# USB.net
KiCad netlist of a schematic drawn in Altium Designer
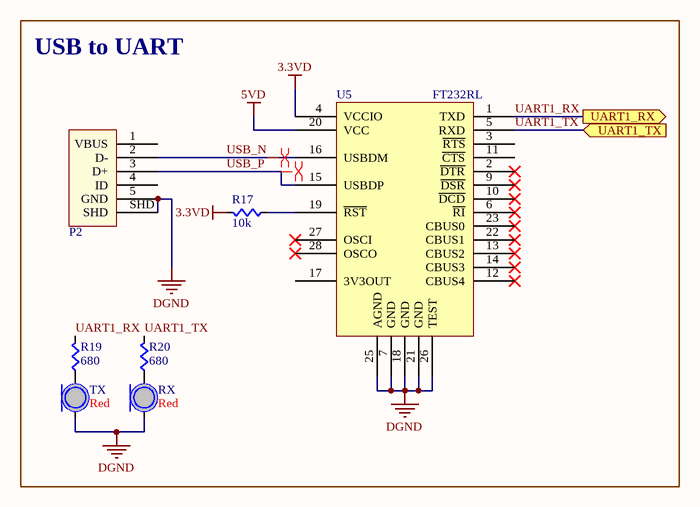
[diagram p0: USB.SchDoc]

(export (version "E")
  (design (tool "Eeschema 10.0.6"))
  (components
    (comp (ref "P2")
      (value "USB Micro")
      (footprint "10118192-0001LF")
      (description "USB Mini B Metal Shield SMT")
      (libsource (lib "SubjuGator8") (part "USB Micro"))
    )
    (comp (ref "R17")
      (value "10k")
      (footprint "RES0603")
      (fields (field (name "Comment") "Res"))
      (libsource (lib "SubjuGator8") (part "Res"))
    )
    (comp (ref "R19")
      (value "680")
      (footprint "RES0603")
      (fields (field (name "Comment") "Res"))
      (libsource (lib "SubjuGator8") (part "Res"))
    )
    (comp (ref "R20")
      (value "680")
      (footprint "RES0603")
      (fields (field (name "Comment") "Res"))
      (libsource (lib "SubjuGator8") (part "Res"))
    )
    (comp (ref "RX")
      (value "LED")
      (footprint "LED0603")
      (fields (field (name "COLOR") "Red"))
      (libsource (lib "SubjuGator8") (part "LED"))
    )
    (comp (ref "TX")
      (value "LED")
      (footprint "LED0603")
      (fields (field (name "COLOR") "Red"))
      (libsource (lib "SubjuGator8") (part "LED"))
    )
    (comp (ref "U5")
      (value "FT232RL")
      (footprint "SSOP_28_N")
      (description "IC USB FS SERIAL UART 28-SSOP")
      (libsource (lib "ICs") (part "FT232RL"))
    )
  )
  (nets
    (net (code "1") (name "/UART1_RX") (class "Default")
      (node (ref "R19") (pin "1") (pinfunction "A_1") (pintype "passive"))
      (node (ref "U5") (pin "1") (pinfunction "TXD_1") (pintype "passive"))
    )
    (net (code "2") (name "/UART1_TX") (class "Default")
      (node (ref "R20") (pin "1") (pinfunction "A_1") (pintype "passive"))
      (node (ref "U5") (pin "5") (pinfunction "RXD_5") (pintype "passive"))
    )
    (net (code "3") (name "/USB_N") (class "Default")
      (node (ref "P2") (pin "2") (pinfunction "D-_2") (pintype "passive"))
      (node (ref "U5") (pin "16") (pinfunction "USBDM_16") (pintype "passive"))
    )
    (net (code "4") (name "/USB_P") (class "Default")
      (node (ref "P2") (pin "3") (pinfunction "D+_3") (pintype "passive"))
      (node (ref "U5") (pin "15") (pinfunction "USBDP_15") (pintype "passive"))
    )
    (net (code "5") (name "3.3VD") (class "Default")
      (node (ref "R17") (pin "1") (pinfunction "A_1") (pintype "passive"))
      (node (ref "U5") (pin "4") (pinfunction "VCCIO_4") (pintype "passive"))
    )
    (net (code "6") (name "5VD") (class "Default")
      (node (ref "U5") (pin "20") (pinfunction "VCC_20") (pintype "passive"))
    )
    (net (code "7") (name "DGND") (class "Default")
      (node (ref "P2") (pin "5") (pinfunction "GND_5") (pintype "passive"))
      (node (ref "P2") (pin "SHD") (pinfunction "SHD_SHD") (pintype "passive"))
      (node (ref "RX") (pin "C") (pinfunction "C_C") (pintype "passive"))
      (node (ref "TX") (pin "C") (pinfunction "C_C") (pintype "passive"))
      (node (ref "U5") (pin "18") (pinfunction "GND_18") (pintype "passive"))
      (node (ref "U5") (pin "21") (pinfunction "GND_21") (pintype "passive"))
      (node (ref "U5") (pin "25") (pinfunction "AGND_25") (pintype "passive"))
      (node (ref "U5") (pin "26") (pinfunction "TEST_26") (pintype "passive"))
      (node (ref "U5") (pin "7") (pinfunction "GND_7") (pintype "passive"))
    )
    (net (code "8") (name "Net-(R17-B)") (class "Default")
      (node (ref "R17") (pin "2") (pinfunction "B_2") (pintype "passive"))
      (node (ref "U5") (pin "19") (pinfunction "~{RST}_19") (pintype "passive"))
    )
    (net (code "9") (name "Net-(R19-B)") (class "Default")
      (node (ref "R19") (pin "2") (pinfunction "B_2") (pintype "passive"))
      (node (ref "TX") (pin "A") (pinfunction "A_A") (pintype "passive"))
    )
    (net (code "10") (name "Net-(R20-B)") (class "Default")
      (node (ref "R20") (pin "2") (pinfunction "B_2") (pintype "passive"))
      (node (ref "RX") (pin "A") (pinfunction "A_A") (pintype "passive"))
    )
    (net (code "11") (name "unconnected-(P2-ID-Pad4)") (class "Default")
      (node (ref "P2") (pin "4") (pinfunction "ID_4") (pintype "passive"))
    )
    (net (code "12") (name "unconnected-(P2-VBUS-Pad1)") (class "Default")
      (node (ref "P2") (pin "1") (pinfunction "VBUS_1") (pintype "passive"))
    )
    (net (code "13") (name "unconnected-(U5-3V3OUT-Pad17)") (class "Default")
      (node (ref "U5") (pin "17") (pinfunction "3V3OUT_17") (pintype "passive"))
    )
    (net (code "14") (name "unconnected-(U5-CBUS0-Pad23)") (class "Default")
      (node (ref "U5") (pin "23") (pinfunction "CBUS0_23") (pintype "passive+no_connect"))
    )
    (net (code "15") (name "unconnected-(U5-CBUS1-Pad22)") (class "Default")
      (node (ref "U5") (pin "22") (pinfunction "CBUS1_22") (pintype "passive+no_connect"))
    )
    (net (code "16") (name "unconnected-(U5-CBUS2-Pad13)") (class "Default")
      (node (ref "U5") (pin "13") (pinfunction "CBUS2_13") (pintype "passive+no_connect"))
    )
    (net (code "17") (name "unconnected-(U5-CBUS3-Pad14)") (class "Default")
      (node (ref "U5") (pin "14") (pinfunction "CBUS3_14") (pintype "passive+no_connect"))
    )
    (net (code "18") (name "unconnected-(U5-CBUS4-Pad12)") (class "Default")
      (node (ref "U5") (pin "12") (pinfunction "CBUS4_12") (pintype "passive+no_connect"))
    )
    (net (code "19") (name "unconnected-(U5-OSCI-Pad27)") (class "Default")
      (node (ref "U5") (pin "27") (pinfunction "OSCI_27") (pintype "passive+no_connect"))
    )
    (net (code "20") (name "unconnected-(U5-OSCO-Pad28)") (class "Default")
      (node (ref "U5") (pin "28") (pinfunction "OSCO_28") (pintype "passive+no_connect"))
    )
    (net (code "21") (name "unconnected-(U5-~{CTS}-Pad11)") (class "Default")
      (node (ref "U5") (pin "11") (pinfunction "~{CTS}_11") (pintype "passive"))
    )
    (net (code "22") (name "unconnected-(U5-~{DCD}-Pad10)") (class "Default")
      (node (ref "U5") (pin "10") (pinfunction "~{DCD}_10") (pintype "passive+no_connect"))
    )
    (net (code "23") (name "unconnected-(U5-~{DSR}-Pad9)") (class "Default")
      (node (ref "U5") (pin "9") (pinfunction "~{DSR}_9") (pintype "passive+no_connect"))
    )
    (net (code "24") (name "unconnected-(U5-~{DTR}-Pad2)") (class "Default")
      (node (ref "U5") (pin "2") (pinfunction "~{DTR}_2") (pintype "passive+no_connect"))
    )
    (net (code "25") (name "unconnected-(U5-~{RI}-Pad6)") (class "Default")
      (node (ref "U5") (pin "6") (pinfunction "~{RI}_6") (pintype "passive+no_connect"))
    )
    (net (code "26") (name "unconnected-(U5-~{RTS}-Pad3)") (class "Default")
      (node (ref "U5") (pin "3") (pinfunction "~{RTS}_3") (pintype "passive"))
    )
  )
)
